# PAL13579.net
KiCad netlist of a schematic drawn in EAGLE
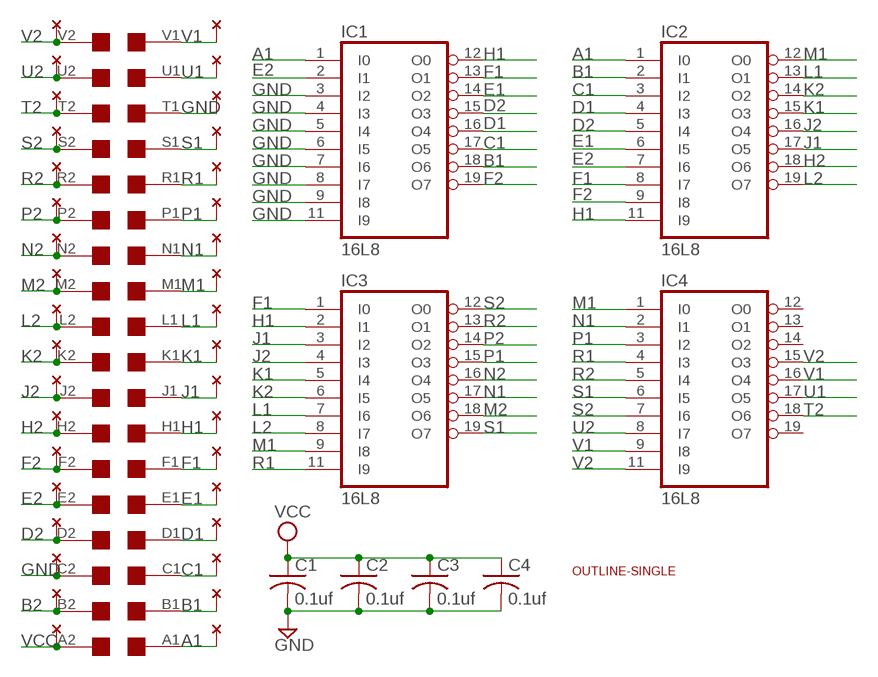
[diagram p0: schematic, sheet 1]

(export (version "E")
  (design (tool "Eeschema 10.0.6"))
  (components
    (comp (ref "C1")
      (value "0.1uf")
      (footprint "eagle-import:C050-025X075")
      (libsource (lib "eagle-import") (part "C-US050-025X075"))
    )
    (comp (ref "C2")
      (value "0.1uf")
      (footprint "eagle-import:C050-025X075")
      (libsource (lib "eagle-import") (part "C-US050-025X075"))
    )
    (comp (ref "C3")
      (value "0.1uf")
      (footprint "eagle-import:C050-025X075")
      (libsource (lib "eagle-import") (part "C-US050-025X075"))
    )
    (comp (ref "C4")
      (value "0.1uf")
      (footprint "eagle-import:C050-025X075")
      (libsource (lib "eagle-import") (part "C-US050-025X075"))
    )
    (comp (ref "IC1")
      (value "16L8")
      (footprint "eagle-import:DIL20")
      (fields (field (name "MF") "TEXAS INSTRUMENTS") (field (name "MPN") "TIBPAL16L8-7CN"))
      (libsource (lib "eagle-import") (part "16L8"))
    )
    (comp (ref "IC2")
      (value "16L8")
      (footprint "eagle-import:DIL20")
      (fields (field (name "MF") "TEXAS INSTRUMENTS") (field (name "MPN") "TIBPAL16L8-7CN"))
      (libsource (lib "eagle-import") (part "16L8"))
    )
    (comp (ref "IC3")
      (value "16L8")
      (footprint "eagle-import:DIL20")
      (fields (field (name "MF") "TEXAS INSTRUMENTS") (field (name "MPN") "TIBPAL16L8-7CN"))
      (libsource (lib "eagle-import") (part "16L8"))
    )
    (comp (ref "IC4")
      (value "16L8")
      (footprint "eagle-import:DIL20")
      (fields (field (name "MF") "TEXAS INSTRUMENTS") (field (name "MPN") "TIBPAL16L8-7CN"))
      (libsource (lib "eagle-import") (part "16L8"))
    )
    (comp (ref "U$1")
      (value "EDGE-2CONNECTOR")
      (footprint "eagle-import:EDGE-CON2")
      (libsource (lib "eagle-import") (part "EDGE-2CONNECTOR"))
    )
    (comp (ref "U$2")
      (value "OUTLINE-SINGLE")
      (footprint "eagle-import:SINGLE")
      (libsource (lib "eagle-import") (part "OUTLINE-SINGLE"))
    )
    (comp (ref "U$4")
      (value "THRU-HOLE2A")
      (footprint "eagle-import:THRU-HOLEA")
      (libsource (lib "eagle-import") (part "THRU-HOLE2A"))
    )
  )
  (nets
    (net (code "1") (name "/A1") (class "Default")
      (node (ref "IC1") (pin "1") (pinfunction "I0_1") (pintype "input"))
      (node (ref "IC2") (pin "1") (pinfunction "I0_1") (pintype "input"))
      (node (ref "U$1") (pin "A1") (pinfunction "1_A1") (pintype "bidirectional"))
      (node (ref "U$4") (pin "A1") (pinfunction "P$1_A1") (pintype "passive"))
    )
    (net (code "2") (name "/B1") (class "Default")
      (node (ref "IC1") (pin "18") (pinfunction "O6_18") (pintype "bidirectional"))
      (node (ref "IC2") (pin "2") (pinfunction "I1_2") (pintype "input"))
      (node (ref "U$1") (pin "B1") (pinfunction "1_B1") (pintype "bidirectional"))
      (node (ref "U$4") (pin "B1") (pinfunction "P$1_B1") (pintype "passive"))
    )
    (net (code "3") (name "/B2") (class "Default")
      (node (ref "U$1") (pin "B2") (pinfunction "1_B2") (pintype "bidirectional"))
      (node (ref "U$4") (pin "B2") (pinfunction "P$1_B2") (pintype "passive"))
    )
    (net (code "4") (name "/C1") (class "Default")
      (node (ref "IC1") (pin "17") (pinfunction "O5_17") (pintype "bidirectional"))
      (node (ref "IC2") (pin "3") (pinfunction "I2_3") (pintype "input"))
      (node (ref "U$1") (pin "C1") (pinfunction "1_C1") (pintype "bidirectional"))
      (node (ref "U$4") (pin "C1") (pinfunction "P$1_C1") (pintype "passive"))
    )
    (net (code "5") (name "/D1") (class "Default")
      (node (ref "IC1") (pin "16") (pinfunction "O4_16") (pintype "bidirectional"))
      (node (ref "IC2") (pin "4") (pinfunction "I3_4") (pintype "input"))
      (node (ref "U$1") (pin "D1") (pinfunction "1_D1") (pintype "bidirectional"))
      (node (ref "U$4") (pin "D1") (pinfunction "P$1_D1") (pintype "passive"))
    )
    (net (code "6") (name "/D2") (class "Default")
      (node (ref "IC1") (pin "15") (pinfunction "O3_15") (pintype "bidirectional"))
      (node (ref "IC2") (pin "5") (pinfunction "I4_5") (pintype "input"))
      (node (ref "U$1") (pin "D2") (pinfunction "1_D2") (pintype "bidirectional"))
      (node (ref "U$4") (pin "D2") (pinfunction "P$1_D2") (pintype "passive"))
    )
    (net (code "7") (name "/E1") (class "Default")
      (node (ref "IC1") (pin "14") (pinfunction "O2_14") (pintype "bidirectional"))
      (node (ref "IC2") (pin "6") (pinfunction "I5_6") (pintype "input"))
      (node (ref "U$1") (pin "E1") (pinfunction "1_E1") (pintype "bidirectional"))
      (node (ref "U$4") (pin "E1") (pinfunction "P$1_E1") (pintype "passive"))
    )
    (net (code "8") (name "/E2") (class "Default")
      (node (ref "IC1") (pin "2") (pinfunction "I1_2") (pintype "input"))
      (node (ref "IC2") (pin "7") (pinfunction "I6_7") (pintype "input"))
      (node (ref "U$1") (pin "E2") (pinfunction "1_E2") (pintype "bidirectional"))
      (node (ref "U$4") (pin "E2") (pinfunction "P$1_E2") (pintype "passive"))
    )
    (net (code "9") (name "/F1") (class "Default")
      (node (ref "IC1") (pin "13") (pinfunction "O1_13") (pintype "bidirectional"))
      (node (ref "IC2") (pin "8") (pinfunction "I7_8") (pintype "input"))
      (node (ref "IC3") (pin "1") (pinfunction "I0_1") (pintype "input"))
      (node (ref "U$1") (pin "F1") (pinfunction "1_F1") (pintype "bidirectional"))
      (node (ref "U$4") (pin "F1") (pinfunction "P$1_F1") (pintype "passive"))
    )
    (net (code "10") (name "/F2") (class "Default")
      (node (ref "IC1") (pin "19") (pinfunction "O7_19") (pintype "output"))
      (node (ref "IC2") (pin "9") (pinfunction "I8_9") (pintype "input"))
      (node (ref "U$1") (pin "F2") (pinfunction "1_F2") (pintype "bidirectional"))
      (node (ref "U$4") (pin "F2") (pinfunction "P$1_F2") (pintype "passive"))
    )
    (net (code "11") (name "/H1") (class "Default")
      (node (ref "IC1") (pin "12") (pinfunction "O0_12") (pintype "output"))
      (node (ref "IC2") (pin "11") (pinfunction "I9_11") (pintype "input"))
      (node (ref "IC3") (pin "2") (pinfunction "I1_2") (pintype "input"))
      (node (ref "U$1") (pin "H1") (pinfunction "1_H1") (pintype "bidirectional"))
      (node (ref "U$4") (pin "H1") (pinfunction "P$1_H1") (pintype "passive"))
    )
    (net (code "12") (name "/H2") (class "Default")
      (node (ref "IC2") (pin "18") (pinfunction "O6_18") (pintype "bidirectional"))
      (node (ref "U$1") (pin "H2") (pinfunction "1_H2") (pintype "bidirectional"))
      (node (ref "U$4") (pin "H2") (pinfunction "P$1_H2") (pintype "passive"))
    )
    (net (code "13") (name "/J1") (class "Default")
      (node (ref "IC2") (pin "17") (pinfunction "O5_17") (pintype "bidirectional"))
      (node (ref "IC3") (pin "3") (pinfunction "I2_3") (pintype "input"))
      (node (ref "U$1") (pin "J1") (pinfunction "1_J1") (pintype "bidirectional"))
      (node (ref "U$4") (pin "J1") (pinfunction "P$1_J1") (pintype "passive"))
    )
    (net (code "14") (name "/J2") (class "Default")
      (node (ref "IC2") (pin "16") (pinfunction "O4_16") (pintype "bidirectional"))
      (node (ref "IC3") (pin "4") (pinfunction "I3_4") (pintype "input"))
      (node (ref "U$1") (pin "J2") (pinfunction "1_J2") (pintype "bidirectional"))
      (node (ref "U$4") (pin "J2") (pinfunction "P$1_J2") (pintype "passive"))
    )
    (net (code "15") (name "/K1") (class "Default")
      (node (ref "IC2") (pin "15") (pinfunction "O3_15") (pintype "bidirectional"))
      (node (ref "IC3") (pin "5") (pinfunction "I4_5") (pintype "input"))
      (node (ref "U$1") (pin "K1") (pinfunction "1_K1") (pintype "bidirectional"))
      (node (ref "U$4") (pin "K1") (pinfunction "P$1_K1") (pintype "passive"))
    )
    (net (code "16") (name "/K2") (class "Default")
      (node (ref "IC2") (pin "14") (pinfunction "O2_14") (pintype "bidirectional"))
      (node (ref "IC3") (pin "6") (pinfunction "I5_6") (pintype "input"))
      (node (ref "U$1") (pin "K2") (pinfunction "1_K2") (pintype "bidirectional"))
      (node (ref "U$4") (pin "K2") (pinfunction "P$1_K2") (pintype "passive"))
    )
    (net (code "17") (name "/L1") (class "Default")
      (node (ref "IC2") (pin "13") (pinfunction "O1_13") (pintype "bidirectional"))
      (node (ref "IC3") (pin "7") (pinfunction "I6_7") (pintype "input"))
      (node (ref "U$1") (pin "L1") (pinfunction "1_L1") (pintype "bidirectional"))
      (node (ref "U$4") (pin "L1") (pinfunction "P$1_L1") (pintype "passive"))
    )
    (net (code "18") (name "/L2") (class "Default")
      (node (ref "IC2") (pin "19") (pinfunction "O7_19") (pintype "output"))
      (node (ref "IC3") (pin "8") (pinfunction "I7_8") (pintype "input"))
      (node (ref "U$1") (pin "L2") (pinfunction "1_L2") (pintype "bidirectional"))
      (node (ref "U$4") (pin "L2") (pinfunction "P$1_L2") (pintype "passive"))
    )
    (net (code "19") (name "/M1") (class "Default")
      (node (ref "IC2") (pin "12") (pinfunction "O0_12") (pintype "output"))
      (node (ref "IC3") (pin "9") (pinfunction "I8_9") (pintype "input"))
      (node (ref "IC4") (pin "1") (pinfunction "I0_1") (pintype "input"))
      (node (ref "U$1") (pin "M1") (pinfunction "1_M1") (pintype "bidirectional"))
      (node (ref "U$4") (pin "M1") (pinfunction "P$1_M1") (pintype "passive"))
    )
    (net (code "20") (name "/M2") (class "Default")
      (node (ref "IC3") (pin "18") (pinfunction "O6_18") (pintype "bidirectional"))
      (node (ref "U$1") (pin "M2") (pinfunction "1_M2") (pintype "bidirectional"))
      (node (ref "U$4") (pin "M2") (pinfunction "P$1_M2") (pintype "passive"))
    )
    (net (code "21") (name "/N1") (class "Default")
      (node (ref "IC3") (pin "17") (pinfunction "O5_17") (pintype "bidirectional"))
      (node (ref "IC4") (pin "2") (pinfunction "I1_2") (pintype "input"))
      (node (ref "U$1") (pin "N1") (pinfunction "1_N1") (pintype "bidirectional"))
      (node (ref "U$4") (pin "N1") (pinfunction "P$1_N1") (pintype "passive"))
    )
    (net (code "22") (name "/N2") (class "Default")
      (node (ref "IC3") (pin "16") (pinfunction "O4_16") (pintype "bidirectional"))
      (node (ref "U$1") (pin "N2") (pinfunction "1_N2") (pintype "bidirectional"))
      (node (ref "U$4") (pin "N2") (pinfunction "P$1_N2") (pintype "passive"))
    )
    (net (code "23") (name "/P1") (class "Default")
      (node (ref "IC3") (pin "15") (pinfunction "O3_15") (pintype "bidirectional"))
      (node (ref "IC4") (pin "3") (pinfunction "I2_3") (pintype "input"))
      (node (ref "U$1") (pin "P1") (pinfunction "1_P1") (pintype "bidirectional"))
      (node (ref "U$4") (pin "P1") (pinfunction "P$1_P1") (pintype "passive"))
    )
    (net (code "24") (name "/P2") (class "Default")
      (node (ref "IC3") (pin "14") (pinfunction "O2_14") (pintype "bidirectional"))
      (node (ref "U$1") (pin "P2") (pinfunction "1_P2") (pintype "bidirectional"))
      (node (ref "U$4") (pin "P2") (pinfunction "P$1_P2") (pintype "passive"))
    )
    (net (code "25") (name "/R1") (class "Default")
      (node (ref "IC3") (pin "11") (pinfunction "I9_11") (pintype "input"))
      (node (ref "IC4") (pin "4") (pinfunction "I3_4") (pintype "input"))
      (node (ref "U$1") (pin "R1") (pinfunction "1_R1") (pintype "bidirectional"))
      (node (ref "U$4") (pin "R1") (pinfunction "P$1_R1") (pintype "passive"))
    )
    (net (code "26") (name "/R2") (class "Default")
      (node (ref "IC3") (pin "13") (pinfunction "O1_13") (pintype "bidirectional"))
      (node (ref "IC4") (pin "5") (pinfunction "I4_5") (pintype "input"))
      (node (ref "U$1") (pin "R2") (pinfunction "1_R2") (pintype "bidirectional"))
      (node (ref "U$4") (pin "R2") (pinfunction "P$1_R2") (pintype "passive"))
    )
    (net (code "27") (name "/S1") (class "Default")
      (node (ref "IC3") (pin "19") (pinfunction "O7_19") (pintype "output"))
      (node (ref "IC4") (pin "6") (pinfunction "I5_6") (pintype "input"))
      (node (ref "U$1") (pin "S1") (pinfunction "1_S1") (pintype "bidirectional"))
      (node (ref "U$4") (pin "S1") (pinfunction "P$1_S1") (pintype "passive"))
    )
    (net (code "28") (name "/S2") (class "Default")
      (node (ref "IC3") (pin "12") (pinfunction "O0_12") (pintype "output"))
      (node (ref "IC4") (pin "7") (pinfunction "I6_7") (pintype "input"))
      (node (ref "U$1") (pin "S2") (pinfunction "1_S2") (pintype "bidirectional"))
      (node (ref "U$4") (pin "S2") (pinfunction "P$1_S2") (pintype "passive"))
    )
    (net (code "29") (name "/T2") (class "Default")
      (node (ref "IC4") (pin "18") (pinfunction "O6_18") (pintype "bidirectional"))
      (node (ref "U$1") (pin "T2") (pinfunction "1_T2") (pintype "bidirectional"))
      (node (ref "U$4") (pin "T2") (pinfunction "P$1_T2") (pintype "passive"))
    )
    (net (code "30") (name "/U1") (class "Default")
      (node (ref "IC4") (pin "17") (pinfunction "O5_17") (pintype "bidirectional"))
      (node (ref "U$1") (pin "U1") (pinfunction "1_U1") (pintype "bidirectional"))
      (node (ref "U$4") (pin "U1") (pinfunction "P$1_U1") (pintype "passive"))
    )
    (net (code "31") (name "/U2") (class "Default")
      (node (ref "IC4") (pin "8") (pinfunction "I7_8") (pintype "input"))
      (node (ref "U$1") (pin "U2") (pinfunction "1_U2") (pintype "bidirectional"))
      (node (ref "U$4") (pin "U2") (pinfunction "P$1_U2") (pintype "passive"))
    )
    (net (code "32") (name "/V1") (class "Default")
      (node (ref "IC4") (pin "16") (pinfunction "O4_16") (pintype "bidirectional"))
      (node (ref "IC4") (pin "9") (pinfunction "I8_9") (pintype "input"))
      (node (ref "U$1") (pin "V1") (pinfunction "1_V1") (pintype "bidirectional"))
      (node (ref "U$4") (pin "V1") (pinfunction "P$1_V1") (pintype "passive"))
    )
    (net (code "33") (name "/V2") (class "Default")
      (node (ref "IC4") (pin "11") (pinfunction "I9_11") (pintype "input"))
      (node (ref "IC4") (pin "15") (pinfunction "O3_15") (pintype "bidirectional"))
      (node (ref "U$1") (pin "V2") (pinfunction "1_V2") (pintype "bidirectional"))
      (node (ref "U$4") (pin "V2") (pinfunction "P$1_V2") (pintype "passive"))
    )
    (net (code "34") (name "GND") (class "Default")
      (node (ref "C1") (pin "2") (pinfunction "2_2") (pintype "passive"))
      (node (ref "C2") (pin "2") (pinfunction "2_2") (pintype "passive"))
      (node (ref "C3") (pin "2") (pinfunction "2_2") (pintype "passive"))
      (node (ref "C4") (pin "2") (pinfunction "2_2") (pintype "passive"))
      (node (ref "IC1") (pin "11") (pinfunction "I9_11") (pintype "input"))
      (node (ref "IC1") (pin "3") (pinfunction "I2_3") (pintype "input"))
      (node (ref "IC1") (pin "4") (pinfunction "I3_4") (pintype "input"))
      (node (ref "IC1") (pin "5") (pinfunction "I4_5") (pintype "input"))
      (node (ref "IC1") (pin "6") (pinfunction "I5_6") (pintype "input"))
      (node (ref "IC1") (pin "7") (pinfunction "I6_7") (pintype "input"))
      (node (ref "IC1") (pin "8") (pinfunction "I7_8") (pintype "input"))
      (node (ref "IC1") (pin "9") (pinfunction "I8_9") (pintype "input"))
      (node (ref "U$1") (pin "C2") (pinfunction "1_C2") (pintype "bidirectional"))
      (node (ref "U$1") (pin "T1") (pinfunction "1_T1") (pintype "bidirectional"))
      (node (ref "U$4") (pin "C2") (pinfunction "P$1_C2") (pintype "passive"))
      (node (ref "U$4") (pin "T1") (pinfunction "P$1_T1") (pintype "passive"))
    )
    (net (code "35") (name "VCC") (class "Default")
      (node (ref "C1") (pin "1") (pinfunction "1_1") (pintype "passive"))
      (node (ref "C2") (pin "1") (pinfunction "1_1") (pintype "passive"))
      (node (ref "C3") (pin "1") (pinfunction "1_1") (pintype "passive"))
      (node (ref "C4") (pin "1") (pinfunction "1_1") (pintype "passive"))
      (node (ref "U$1") (pin "A2") (pinfunction "1_A2") (pintype "bidirectional"))
      (node (ref "U$4") (pin "A2") (pinfunction "P$1_A2") (pintype "passive"))
    )
    (net (code "36") (name "unconnected-(IC4A-O0-Pad12)") (class "Default")
      (node (ref "IC4") (pin "12") (pinfunction "O0_12") (pintype "output"))
    )
    (net (code "37") (name "unconnected-(IC4A-O1-Pad13)") (class "Default")
      (node (ref "IC4") (pin "13") (pinfunction "O1_13") (pintype "bidirectional"))
    )
    (net (code "38") (name "unconnected-(IC4A-O2-Pad14)") (class "Default")
      (node (ref "IC4") (pin "14") (pinfunction "O2_14") (pintype "bidirectional"))
    )
    (net (code "39") (name "unconnected-(IC4A-O7-Pad19)") (class "Default")
      (node (ref "IC4") (pin "19") (pinfunction "O7_19") (pintype "output"))
    )
  )
)
